# SparkFun_Dev_ESP32_C3.net
KiCad netlist of a schematic drawn in EAGLE
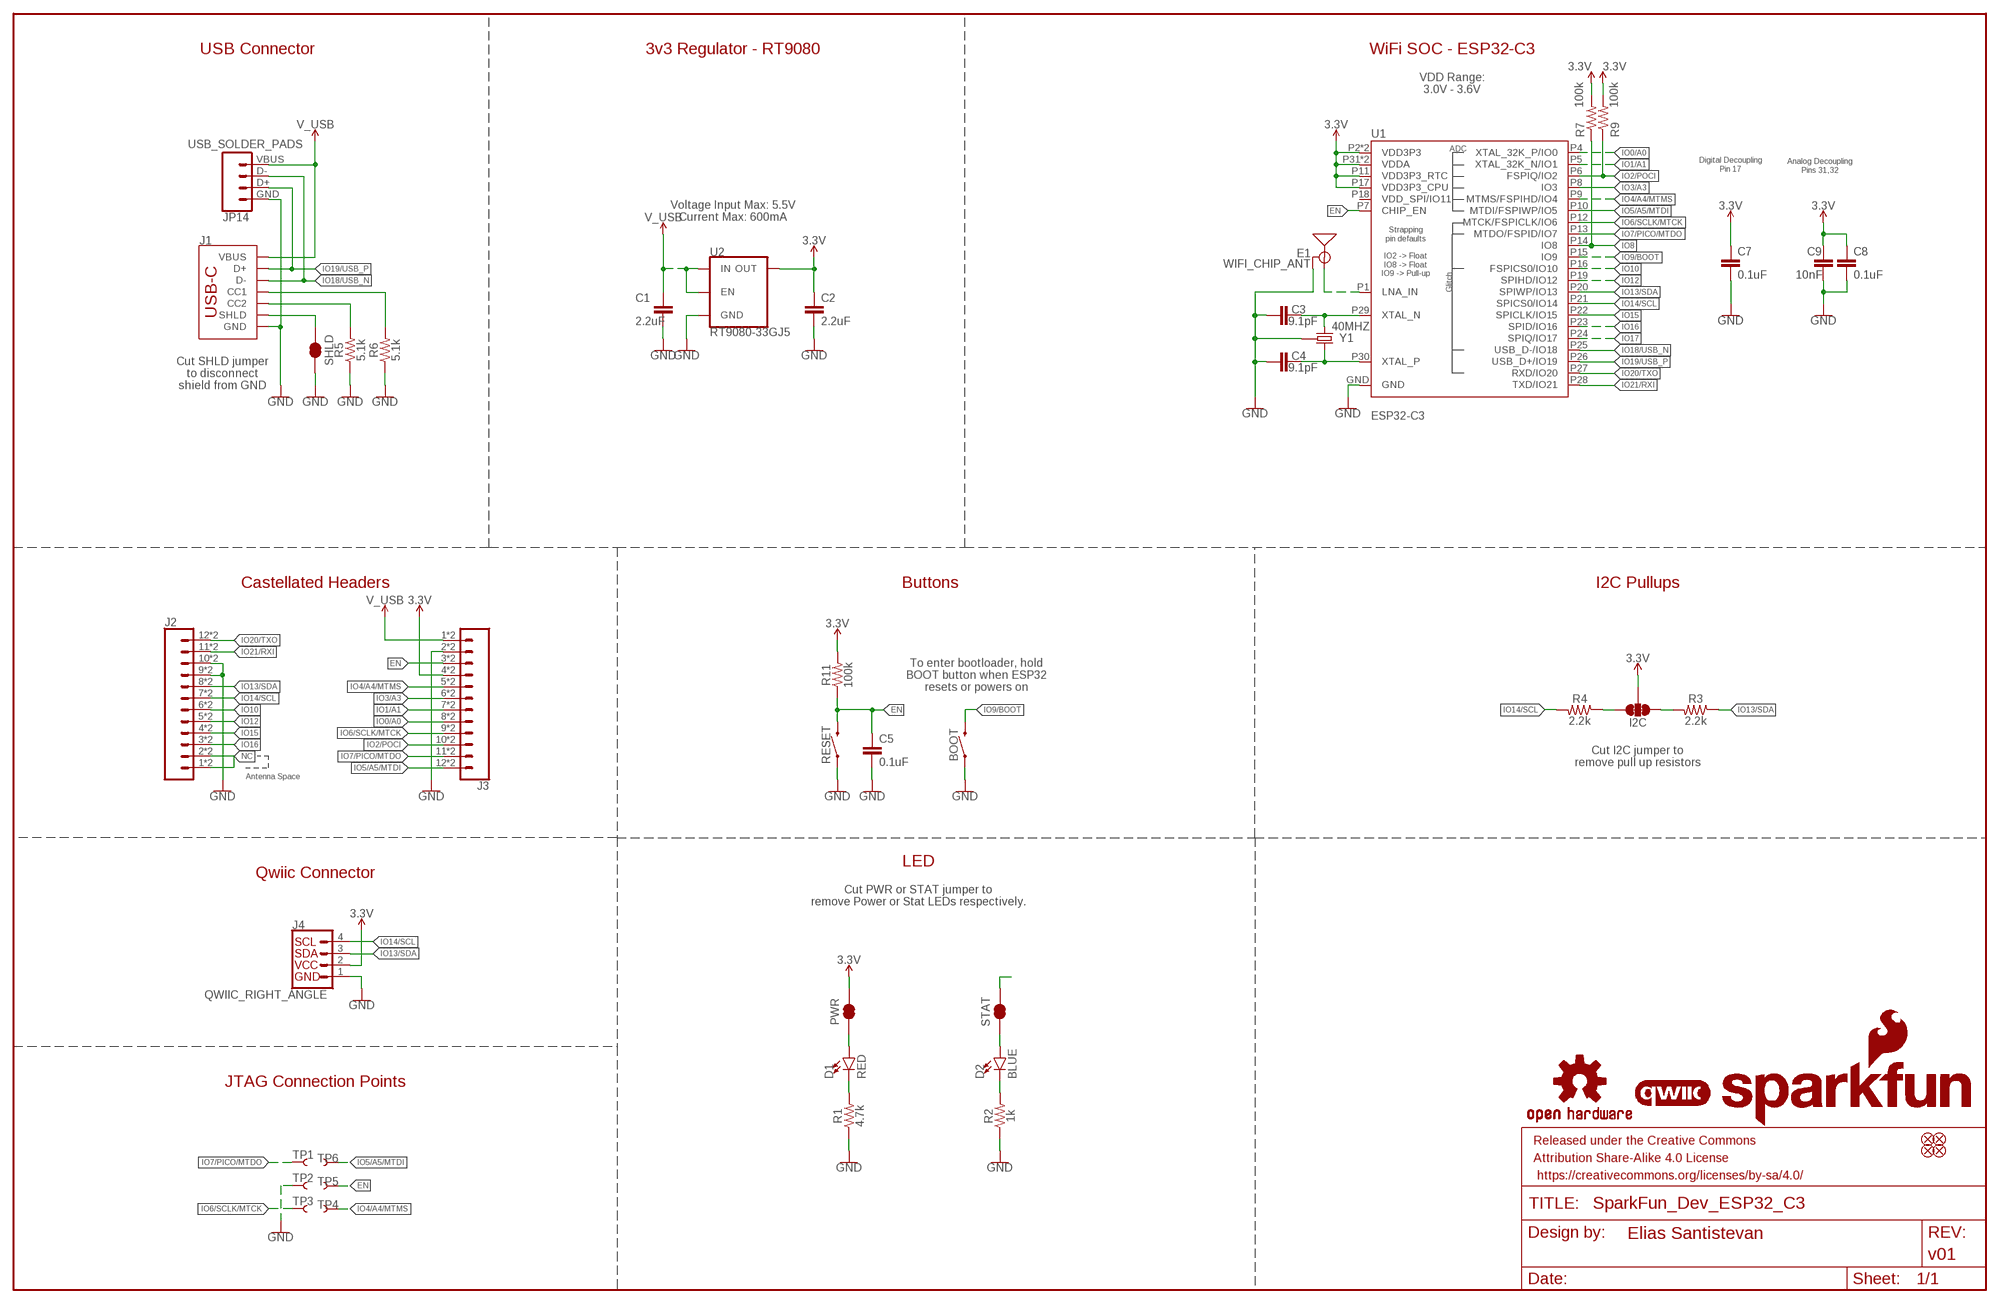
[diagram p0: schematic, sheet 1]

(export (version "E")
  (design (tool "Eeschema 10.0.6"))
  (components
    (comp (ref "BOOT")
      (value "MOMENTARY-SWITCH-SPST-SMD-4.6X2.8MM")
      (footprint "eagle-import:TACTILE_SWITCH_SMD_4.6X2.8MM")
      (libsource (lib "eagle-import") (part "MOMENTARY-SWITCH-SPST-SMD-4.6X2.8MM"))
    )
    (comp (ref "C1")
      (value "2.2uF")
      (footprint "eagle-import:0402-TIGHT")
      (libsource (lib "eagle-import") (part "2.2UF-0402_TIGHT-10V-10%-X5R"))
    )
    (comp (ref "C2")
      (value "2.2uF")
      (footprint "eagle-import:0402-TIGHT")
      (libsource (lib "eagle-import") (part "2.2UF-0402_TIGHT-10V-10%-X5R"))
    )
    (comp (ref "C3")
      (value "9.1pF")
      (footprint "eagle-import:0402-TIGHT")
      (fields (field (name "MOUSER_PART") "609-500R07S9R1CV4T"))
      (libsource (lib "eagle-import") (part "9.1PF-0402-TIGHT"))
    )
    (comp (ref "C4")
      (value "9.1pF")
      (footprint "eagle-import:0402-TIGHT")
      (fields (field (name "MOUSER_PART") "609-500R07S9R1CV4T"))
      (libsource (lib "eagle-import") (part "9.1PF-0402-TIGHT"))
    )
    (comp (ref "C5")
      (value "0.1uF")
      (footprint "eagle-import:0402-TIGHT")
      (libsource (lib "eagle-import") (part "0.1UF-0402T-6.3V-10%-X7R"))
    )
    (comp (ref "C7")
      (value "0.1uF")
      (footprint "eagle-import:0402-TIGHT")
      (libsource (lib "eagle-import") (part "0.1UF-0402T-16V-10%"))
    )
    (comp (ref "C8")
      (value "0.1uF")
      (footprint "eagle-import:0402-TIGHT")
      (libsource (lib "eagle-import") (part "0.1UF-0402T-16V-10%"))
    )
    (comp (ref "C9")
      (value "10nF")
      (footprint "eagle-import:0402-TIGHT")
      (libsource (lib "eagle-import") (part "10NF-0402T-25V-10%"))
    )
    (comp (ref "D1")
      (value "RED")
      (footprint "eagle-import:LED-0603")
      (libsource (lib "eagle-import") (part "LED-RED_0603-KB"))
    )
    (comp (ref "D2")
      (value "BLUE")
      (footprint "eagle-import:LED-0603")
      (libsource (lib "eagle-import") (part "LED-BLUE0603"))
    )
    (comp (ref "E1")
      (value "WIFI_CHIP_ANT")
      (footprint "eagle-import:CHIP_ANT_NO_COURTYARD")
      (libsource (lib "eagle-import") (part "WIFI_CHIP_ANT"))
    )
    (comp (ref "FD1")
      (value "FIDUCIALUFIDUCIAL")
      (footprint "eagle-import:FIDUCIAL-MICRO")
      (libsource (lib "eagle-import") (part "FIDUCIALUFIDUCIAL"))
    )
    (comp (ref "FD2")
      (value "FIDUCIALUFIDUCIAL")
      (footprint "eagle-import:FIDUCIAL-MICRO")
      (libsource (lib "eagle-import") (part "FIDUCIALUFIDUCIAL"))
    )
    (comp (ref "FD3")
      (value "FIDUCIALUFIDUCIAL")
      (footprint "eagle-import:FIDUCIAL-MICRO")
      (libsource (lib "eagle-import") (part "FIDUCIALUFIDUCIAL"))
    )
    (comp (ref "FD4")
      (value "FIDUCIALUFIDUCIAL")
      (footprint "eagle-import:FIDUCIAL-MICRO")
      (libsource (lib "eagle-import") (part "FIDUCIALUFIDUCIAL"))
    )
    (comp (ref "FRAME2")
      (value "FRAME-LEDGER")
      (footprint "eagle-import:CREATIVE_COMMONS")
      (fields (field (name "DESIGNER") "Elias Santistevan") (field (name "REV") "v01"))
      (libsource (lib "eagle-import") (part "FRAME-LEDGER"))
    )
    (comp (ref "I2C")
      (value "JUMPER-SMT_3_2-NC_TRACE_SILK")
      (footprint "eagle-import:SMT-JUMPER_3_2-NC_TRACE_SILK")
      (libsource (lib "eagle-import") (part "JUMPER-SMT_3_2-NC_TRACE_SILK"))
    )
    (comp (ref "J1")
      (value "USB Female Type C Connector")
      (footprint "eagle-import:USB-C-16P_4LAYER-PADS")
      (libsource (lib "eagle-import") (part "USB_C_4-LAYER_PADS"))
    )
    (comp (ref "J2")
      (value "CONN_12CASTELLATED")
      (footprint "eagle-import:1X12_CASTELLATED")
      (libsource (lib "eagle-import") (part "CONN_12CASTELLATED"))
    )
    (comp (ref "J3")
      (value "CONN_12CASTELLATED")
      (footprint "eagle-import:1X12_CASTELLATED")
      (libsource (lib "eagle-import") (part "CONN_12CASTELLATED"))
    )
    (comp (ref "J4")
      (value "QWIIC_RIGHT_ANGLE")
      (footprint "eagle-import:JST04_1MM_RA")
      (libsource (lib "eagle-import") (part "QWIIC_CONNECTORJS-1MM"))
    )
    (comp (ref "JP14")
      (value "USB_SOLDER_PADS")
      (footprint "eagle-import:USB-SOLDER-PADS")
      (libsource (lib "eagle-import") (part "USB_SOLDER_PADS"))
    )
    (comp (ref "LOGO1")
      (value "SFE_LOGO_NAME_FLAMEBLANK")
      (footprint "eagle-import:BLANK")
      (libsource (lib "eagle-import") (part "SFE_LOGO_NAME_FLAMEBLANK"))
    )
    (comp (ref "LOGO2")
      (value "QWIIC_LOGO_3MM")
      (footprint "eagle-import:QWIIC_3MM")
      (libsource (lib "eagle-import") (part "QWIIC_LOGO_3MM"))
    )
    (comp (ref "LOGO3")
      (value "OSHW-LOGOS")
      (footprint "eagle-import:OSHW-LOGO-S")
      (libsource (lib "eagle-import") (part "OSHW-LOGOS"))
    )
    (comp (ref "PWR")
      (value "JUMPER-SMT_2_NC_TRACE_SILK")
      (footprint "eagle-import:SMT-JUMPER_2_NC_TRACE_SILK")
      (libsource (lib "eagle-import") (part "JUMPER-SMT_2_NC_TRACE_SILK"))
    )
    (comp (ref "R1")
      (value "4.7k")
      (footprint "eagle-import:0402-TIGHT")
      (libsource (lib "eagle-import") (part "4.7KOHM-0402T-1/16W-1%"))
    )
    (comp (ref "R2")
      (value "1k")
      (footprint "eagle-import:0402-TIGHT")
      (libsource (lib "eagle-import") (part "1KOHM-0402T-1/16W-1%"))
    )
    (comp (ref "R3")
      (value "2.2k")
      (footprint "eagle-import:0402-TIGHT")
      (libsource (lib "eagle-import") (part "2.2KOHM-0402T-1/16W-1%"))
    )
    (comp (ref "R4")
      (value "2.2k")
      (footprint "eagle-import:0402-TIGHT")
      (libsource (lib "eagle-import") (part "2.2KOHM-0402T-1/16W-1%"))
    )
    (comp (ref "R5")
      (value "5.1k")
      (footprint "eagle-import:0402-TIGHT")
      (libsource (lib "eagle-import") (part "5.1KOHM-0402T-1/16W-1%"))
    )
    (comp (ref "R6")
      (value "5.1k")
      (footprint "eagle-import:0402-TIGHT")
      (libsource (lib "eagle-import") (part "5.1KOHM-0402T-1/16W-1%"))
    )
    (comp (ref "R7")
      (value "100k")
      (footprint "eagle-import:0402-TIGHT")
      (libsource (lib "eagle-import") (part "100KOHM-0402T-1/16W-1%"))
    )
    (comp (ref "R9")
      (value "100k")
      (footprint "eagle-import:0402-TIGHT")
      (libsource (lib "eagle-import") (part "100KOHM-0402T-1/16W-1%"))
    )
    (comp (ref "R11")
      (value "100k")
      (footprint "eagle-import:0402-TIGHT")
      (libsource (lib "eagle-import") (part "100KOHM-0402T-1/16W-1%"))
    )
    (comp (ref "RESET")
      (value "MOMENTARY-SWITCH-SPST-SMD-4.6X2.8MM")
      (footprint "eagle-import:TACTILE_SWITCH_SMD_4.6X2.8MM")
      (libsource (lib "eagle-import") (part "MOMENTARY-SWITCH-SPST-SMD-4.6X2.8MM"))
    )
    (comp (ref "SHLD")
      (value "JUMPER-SMT_2_NC_TRACE_SILK")
      (footprint "eagle-import:SMT-JUMPER_2_NC_TRACE_SILK")
      (libsource (lib "eagle-import") (part "JUMPER-SMT_2_NC_TRACE_SILK"))
    )
    (comp (ref "STAT")
      (value "JUMPER-SMT_2_NC_TRACE_SILK")
      (footprint "eagle-import:SMT-JUMPER_2_NC_TRACE_SILK")
      (libsource (lib "eagle-import") (part "JUMPER-SMT_2_NC_TRACE_SILK"))
    )
    (comp (ref "TP1")
      (value "TEST-POINT3X5")
      (footprint "eagle-import:PAD.03X.05")
      (libsource (lib "eagle-import") (part "TEST-POINT3X5"))
    )
    (comp (ref "TP2")
      (value "TEST-POINT3X5")
      (footprint "eagle-import:PAD.03X.05")
      (libsource (lib "eagle-import") (part "TEST-POINT3X5"))
    )
    (comp (ref "TP3")
      (value "TEST-POINT3X5")
      (footprint "eagle-import:PAD.03X.05")
      (libsource (lib "eagle-import") (part "TEST-POINT3X5"))
    )
    (comp (ref "TP4")
      (value "TEST-POINT3X5")
      (footprint "eagle-import:PAD.03X.05")
      (libsource (lib "eagle-import") (part "TEST-POINT3X5"))
    )
    (comp (ref "TP5")
      (value "TEST-POINT3X5")
      (footprint "eagle-import:PAD.03X.05")
      (libsource (lib "eagle-import") (part "TEST-POINT3X5"))
    )
    (comp (ref "TP6")
      (value "TEST-POINT3X5")
      (footprint "eagle-import:PAD.03X.05")
      (libsource (lib "eagle-import") (part "TEST-POINT3X5"))
    )
    (comp (ref "U1")
      (value "ESP32-C3")
      (footprint "eagle-import:QFN32")
      (libsource (lib "eagle-import") (part "ESP32-C3"))
    )
    (comp (ref "U2")
      (value "RT9080-33GJ5")
      (footprint "eagle-import:SOT23-5")
      (libsource (lib "eagle-import") (part "V_REG_RT9080"))
    )
    (comp (ref "Y1")
      (value "40MHZ")
      (footprint "eagle-import:CRYSTAL-SMD-2X2.5MM")
      (libsource (lib "eagle-import") (part "CRYSTAL-40MHZ-SMD-2X2.5MM"))
    )
  )
  (nets
    (net (code "1") (name "3.3V") (class "Default")
      (node (ref "C2") (pin "1") (pinfunction "1_1") (pintype "passive"))
      (node (ref "C7") (pin "1") (pinfunction "1_1") (pintype "passive"))
      (node (ref "C8") (pin "1") (pinfunction "1_1") (pintype "passive"))
      (node (ref "C9") (pin "1") (pinfunction "1_1") (pintype "passive"))
      (node (ref "I2C") (pin "2") (pinfunction "2_2") (pintype "passive"))
      (node (ref "J3") (pin "4") (pinfunction "4_4") (pintype "passive"))
      (node (ref "J3") (pin "4B") (pinfunction "4_4B") (pintype "passive"))
      (node (ref "J4") (pin "2") (pinfunction "2_2") (pintype "power_in"))
      (node (ref "PWR") (pin "2") (pinfunction "2_2") (pintype "passive"))
      (node (ref "R11") (pin "2") (pinfunction "2_2") (pintype "passive"))
      (node (ref "R7") (pin "2") (pinfunction "2_2") (pintype "passive"))
      (node (ref "R9") (pin "2") (pinfunction "2_2") (pintype "passive"))
      (node (ref "U1") (pin "P11") (pinfunction "VDD3P3_RTC_P11") (pintype "bidirectional"))
      (node (ref "U1") (pin "P17") (pinfunction "VDD3P3_CPU_P17") (pintype "bidirectional"))
      (node (ref "U1") (pin "P2") (pinfunction "VDD3P3_P2") (pintype "bidirectional"))
      (node (ref "U1") (pin "P3") (pinfunction "VDD3P3_P3") (pintype "bidirectional"))
      (node (ref "U1") (pin "P31") (pinfunction "VDDA_P31") (pintype "bidirectional"))
      (node (ref "U1") (pin "P32") (pinfunction "VDDA_P32") (pintype "bidirectional"))
      (node (ref "U2") (pin "5") (pinfunction "OUT_5") (pintype "passive"))
    )
    (net (code "2") (name "EN") (class "Default")
      (node (ref "C5") (pin "1") (pinfunction "1_1") (pintype "passive"))
      (node (ref "J3") (pin "3") (pinfunction "3_3") (pintype "passive"))
      (node (ref "J3") (pin "3B") (pinfunction "3_3B") (pintype "passive"))
      (node (ref "R11") (pin "1") (pinfunction "1_1") (pintype "passive"))
      (node (ref "RESET") (pin "3") (pinfunction "2_3") (pintype "passive"))
      (node (ref "RESET") (pin "4") (pinfunction "2_4") (pintype "passive"))
      (node (ref "TP5") (pin "1") (pinfunction "1_1") (pintype "bidirectional"))
      (node (ref "U1") (pin "P7") (pinfunction "CHIP_EN_P7") (pintype "bidirectional"))
    )
    (net (code "3") (name "GND") (class "Default")
      (node (ref "BOOT") (pin "1") (pinfunction "1_1") (pintype "passive"))
      (node (ref "BOOT") (pin "2") (pinfunction "1_2") (pintype "passive"))
      (node (ref "C1") (pin "2") (pinfunction "2_2") (pintype "passive"))
      (node (ref "C2") (pin "2") (pinfunction "2_2") (pintype "passive"))
      (node (ref "C3") (pin "1") (pinfunction "1_1") (pintype "passive"))
      (node (ref "C4") (pin "1") (pinfunction "1_1") (pintype "passive"))
      (node (ref "C5") (pin "2") (pinfunction "2_2") (pintype "passive"))
      (node (ref "C7") (pin "2") (pinfunction "2_2") (pintype "passive"))
      (node (ref "C8") (pin "2") (pinfunction "2_2") (pintype "passive"))
      (node (ref "C9") (pin "2") (pinfunction "2_2") (pintype "passive"))
      (node (ref "E1") (pin "P3") (pinfunction "GND_P3") (pintype "bidirectional"))
      (node (ref "E1") (pin "P4") (pinfunction "GND_P4") (pintype "bidirectional"))
      (node (ref "J1") (pin "GND") (pinfunction "GND_GND") (pintype "bidirectional"))
      (node (ref "J1") (pin "GND2") (pinfunction "GND_GND2") (pintype "bidirectional"))
      (node (ref "J2") (pin "10") (pinfunction "10_10") (pintype "passive"))
      (node (ref "J2") (pin "10B") (pinfunction "10_10B") (pintype "passive"))
      (node (ref "J2") (pin "9") (pinfunction "9_9") (pintype "passive"))
      (node (ref "J2") (pin "9B") (pinfunction "9_9B") (pintype "passive"))
      (node (ref "J3") (pin "2") (pinfunction "2_2") (pintype "passive"))
      (node (ref "J3") (pin "2B") (pinfunction "2_2B") (pintype "passive"))
      (node (ref "J4") (pin "1") (pinfunction "1_1") (pintype "power_in"))
      (node (ref "JP14") (pin "GND") (pinfunction "4_GND") (pintype "passive"))
      (node (ref "R1") (pin "1") (pinfunction "1_1") (pintype "passive"))
      (node (ref "R2") (pin "1") (pinfunction "1_1") (pintype "passive"))
      (node (ref "R5") (pin "1") (pinfunction "1_1") (pintype "passive"))
      (node (ref "R6") (pin "1") (pinfunction "1_1") (pintype "passive"))
      (node (ref "RESET") (pin "1") (pinfunction "1_1") (pintype "passive"))
      (node (ref "RESET") (pin "2") (pinfunction "1_2") (pintype "passive"))
      (node (ref "SHLD") (pin "2") (pinfunction "2_2") (pintype "passive"))
      (node (ref "TP2") (pin "1") (pinfunction "1_1") (pintype "bidirectional"))
      (node (ref "U1") (pin "GND") (pinfunction "GND_GND") (pintype "bidirectional"))
      (node (ref "U2") (pin "2") (pinfunction "GND_2") (pintype "input"))
      (node (ref "Y1") (pin "P2") (pinfunction "GND_P2") (pintype "power_in"))
      (node (ref "Y1") (pin "P4") (pinfunction "GND_P4") (pintype "power_in"))
    )
    (net (code "4") (name "IO0{slash}A0") (class "Default")
      (node (ref "J3") (pin "8") (pinfunction "8_8") (pintype "passive"))
      (node (ref "J3") (pin "8B") (pinfunction "8_8B") (pintype "passive"))
      (node (ref "U1") (pin "P4") (pinfunction "XTAL_32K_P/IO0_P4") (pintype "bidirectional"))
    )
    (net (code "5") (name "IO1{slash}A1") (class "Default")
      (node (ref "J3") (pin "7") (pinfunction "7_7") (pintype "passive"))
      (node (ref "J3") (pin "7B") (pinfunction "7_7B") (pintype "passive"))
      (node (ref "U1") (pin "P5") (pinfunction "XTAL_32K_N/IO1_P5") (pintype "bidirectional"))
    )
    (net (code "6") (name "IO2{slash}POCI") (class "Default")
      (node (ref "J3") (pin "10") (pinfunction "10_10") (pintype "passive"))
      (node (ref "J3") (pin "10B") (pinfunction "10_10B") (pintype "passive"))
      (node (ref "R9") (pin "1") (pinfunction "1_1") (pintype "passive"))
      (node (ref "U1") (pin "P6") (pinfunction "FSPIQ/IO2_P6") (pintype "bidirectional"))
    )
    (net (code "7") (name "IO3{slash}A3") (class "Default")
      (node (ref "J3") (pin "6") (pinfunction "6_6") (pintype "passive"))
      (node (ref "J3") (pin "6B") (pinfunction "6_6B") (pintype "passive"))
      (node (ref "U1") (pin "P8") (pinfunction "IO3_P8") (pintype "bidirectional"))
    )
    (net (code "8") (name "IO4{slash}A4{slash}MTMS") (class "Default")
      (node (ref "J3") (pin "5") (pinfunction "5_5") (pintype "passive"))
      (node (ref "J3") (pin "5B") (pinfunction "5_5B") (pintype "passive"))
      (node (ref "TP4") (pin "1") (pinfunction "1_1") (pintype "bidirectional"))
      (node (ref "U1") (pin "P9") (pinfunction "MTMS/FSPIHD/IO4_P9") (pintype "bidirectional"))
    )
    (net (code "9") (name "IO5{slash}A5{slash}MTDI") (class "Default")
      (node (ref "J3") (pin "12") (pinfunction "12_12") (pintype "passive"))
      (node (ref "J3") (pin "12B") (pinfunction "12_12B") (pintype "passive"))
      (node (ref "TP6") (pin "1") (pinfunction "1_1") (pintype "bidirectional"))
      (node (ref "U1") (pin "P10") (pinfunction "MTDI/FSPIWP/IO5_P10") (pintype "bidirectional"))
    )
    (net (code "10") (name "IO6{slash}SCLK{slash}MTCK") (class "Default")
      (node (ref "J3") (pin "9") (pinfunction "9_9") (pintype "passive"))
      (node (ref "J3") (pin "9B") (pinfunction "9_9B") (pintype "passive"))
      (node (ref "TP3") (pin "1") (pinfunction "1_1") (pintype "bidirectional"))
      (node (ref "U1") (pin "P12") (pinfunction "MTCK/FSPICLK/IO6_P12") (pintype "bidirectional"))
    )
    (net (code "11") (name "IO7{slash}PICO{slash}MTDO") (class "Default")
      (node (ref "J3") (pin "11") (pinfunction "11_11") (pintype "passive"))
      (node (ref "J3") (pin "11B") (pinfunction "11_11B") (pintype "passive"))
      (node (ref "TP1") (pin "1") (pinfunction "1_1") (pintype "bidirectional"))
      (node (ref "U1") (pin "P13") (pinfunction "MTDO/FSPID/IO7_P13") (pintype "bidirectional"))
    )
    (net (code "12") (name "IO8") (class "Default")
      (node (ref "R7") (pin "1") (pinfunction "1_1") (pintype "passive"))
      (node (ref "U1") (pin "P14") (pinfunction "IO8_P14") (pintype "bidirectional"))
    )
    (net (code "13") (name "IO9{slash}BOOT") (class "Default")
      (node (ref "BOOT") (pin "3") (pinfunction "2_3") (pintype "passive"))
      (node (ref "BOOT") (pin "4") (pinfunction "2_4") (pintype "passive"))
      (node (ref "U1") (pin "P15") (pinfunction "IO9_P15") (pintype "bidirectional"))
    )
    (net (code "14") (name "IO10") (class "Default")
      (node (ref "J2") (pin "6") (pinfunction "6_6") (pintype "passive"))
      (node (ref "J2") (pin "6B") (pinfunction "6_6B") (pintype "passive"))
      (node (ref "U1") (pin "P16") (pinfunction "FSPICS0/IO10_P16") (pintype "bidirectional"))
    )
    (net (code "15") (name "IO12") (class "Default")
      (node (ref "J2") (pin "5") (pinfunction "5_5") (pintype "passive"))
      (node (ref "J2") (pin "5B") (pinfunction "5_5B") (pintype "passive"))
      (node (ref "U1") (pin "P19") (pinfunction "SPIHD/IO12_P19") (pintype "bidirectional"))
    )
    (net (code "16") (name "IO13{slash}SDA") (class "Default")
      (node (ref "J2") (pin "8") (pinfunction "8_8") (pintype "passive"))
      (node (ref "J2") (pin "8B") (pinfunction "8_8B") (pintype "passive"))
      (node (ref "J4") (pin "3") (pinfunction "3_3") (pintype "passive"))
      (node (ref "R3") (pin "1") (pinfunction "1_1") (pintype "passive"))
      (node (ref "U1") (pin "P20") (pinfunction "SPIWP/IO13_P20") (pintype "bidirectional"))
    )
    (net (code "17") (name "IO14{slash}SCL") (class "Default")
      (node (ref "J2") (pin "7") (pinfunction "7_7") (pintype "passive"))
      (node (ref "J2") (pin "7B") (pinfunction "7_7B") (pintype "passive"))
      (node (ref "J4") (pin "4") (pinfunction "4_4") (pintype "passive"))
      (node (ref "R4") (pin "2") (pinfunction "2_2") (pintype "passive"))
      (node (ref "U1") (pin "P21") (pinfunction "SPICS0/IO14_P21") (pintype "bidirectional"))
    )
    (net (code "18") (name "IO15") (class "Default")
      (node (ref "J2") (pin "4") (pinfunction "4_4") (pintype "passive"))
      (node (ref "J2") (pin "4B") (pinfunction "4_4B") (pintype "passive"))
      (node (ref "U1") (pin "P22") (pinfunction "SPICLK/IO15_P22") (pintype "bidirectional"))
    )
    (net (code "19") (name "IO16") (class "Default")
      (node (ref "J2") (pin "3") (pinfunction "3_3") (pintype "passive"))
      (node (ref "J2") (pin "3B") (pinfunction "3_3B") (pintype "passive"))
      (node (ref "U1") (pin "P23") (pinfunction "SPID/IO16_P23") (pintype "bidirectional"))
    )
    (net (code "20") (name "IO17") (class "Default")
      (node (ref "U1") (pin "P24") (pinfunction "SPIQ/IO17_P24") (pintype "bidirectional"))
    )
    (net (code "21") (name "IO18{slash}USB_N") (class "Default")
      (node (ref "J1") (pin "A7") (pinfunction "D-_A7") (pintype "bidirectional"))
      (node (ref "J1") (pin "B7") (pinfunction "D-_B7") (pintype "bidirectional"))
      (node (ref "JP14") (pin "D-") (pinfunction "2_D-") (pintype "passive"))
      (node (ref "U1") (pin "P25") (pinfunction "USB_D-/IO18_P25") (pintype "bidirectional"))
    )
    (net (code "22") (name "IO19{slash}USB_P") (class "Default")
      (node (ref "J1") (pin "A6") (pinfunction "D+_A6") (pintype "bidirectional"))
      (node (ref "J1") (pin "B6") (pinfunction "D+_B6") (pintype "bidirectional"))
      (node (ref "JP14") (pin "D+") (pinfunction "3_D+") (pintype "passive"))
      (node (ref "U1") (pin "P26") (pinfunction "USB_D+/IO19_P26") (pintype "bidirectional"))
    )
    (net (code "23") (name "IO20{slash}TXO") (class "Default")
      (node (ref "J2") (pin "12") (pinfunction "12_12") (pintype "passive"))
      (node (ref "J2") (pin "12B") (pinfunction "12_12B") (pintype "passive"))
      (node (ref "U1") (pin "P27") (pinfunction "RXD/IO20_P27") (pintype "bidirectional"))
    )
    (net (code "24") (name "IO21{slash}RXI") (class "Default")
      (node (ref "J2") (pin "11") (pinfunction "11_11") (pintype "passive"))
      (node (ref "J2") (pin "11B") (pinfunction "11_11B") (pintype "passive"))
      (node (ref "U1") (pin "P28") (pinfunction "TXD/IO21_P28") (pintype "bidirectional"))
    )
    (net (code "25") (name "NC") (class "Default")
      (node (ref "J2") (pin "1") (pinfunction "1_1") (pintype "passive"))
      (node (ref "J2") (pin "1B") (pinfunction "1_1B") (pintype "passive"))
      (node (ref "J2") (pin "2") (pinfunction "2_2") (pintype "passive"))
      (node (ref "J2") (pin "2B") (pinfunction "2_2B") (pintype "passive"))
    )
    (net (code "26") (name "Net-(D1-PadA)") (class "Default")
      (node (ref "D1") (pin "A") (pinfunction "A_A") (pintype "passive"))
      (node (ref "PWR") (pin "1") (pinfunction "1_1") (pintype "passive"))
    )
    (net (code "27") (name "Net-(D1-PadC)") (class "Default")
      (node (ref "D1") (pin "C") (pinfunction "C_C") (pintype "passive"))
      (node (ref "R1") (pin "2") (pinfunction "2_2") (pintype "passive"))
    )
    (net (code "28") (name "Net-(D2-PadA)") (class "Default")
      (node (ref "D2") (pin "A") (pinfunction "A_A") (pintype "passive"))
      (node (ref "STAT") (pin "1") (pinfunction "1_1") (pintype "passive"))
    )
    (net (code "29") (name "Net-(D2-PadC)") (class "Default")
      (node (ref "D2") (pin "C") (pinfunction "C_C") (pintype "passive"))
      (node (ref "R2") (pin "2") (pinfunction "2_2") (pintype "passive"))
    )
    (net (code "30") (name "Net-(E1-SIGNAL)") (class "Default")
      (node (ref "E1") (pin "P1") (pinfunction "SIGNAL_P1") (pintype "bidirectional"))
      (node (ref "U1") (pin "P1") (pinfunction "LNA_IN_P1") (pintype "bidirectional"))
    )
    (net (code "31") (name "Net-(I2C-Pad1)") (class "Default")
      (node (ref "I2C") (pin "1") (pinfunction "1_1") (pintype "passive"))
      (node (ref "R4") (pin "1") (pinfunction "1_1") (pintype "passive"))
    )
    (net (code "32") (name "Net-(I2C-Pad3)") (class "Default")
      (node (ref "I2C") (pin "3") (pinfunction "3_3") (pintype "passive"))
      (node (ref "R3") (pin "2") (pinfunction "2_2") (pintype "passive"))
    )
    (net (code "33") (name "Net-(J1-CC1)") (class "Default")
      (node (ref "J1") (pin "A5") (pinfunction "CC1_A5") (pintype "bidirectional"))
      (node (ref "R6") (pin "2") (pinfunction "2_2") (pintype "passive"))
    )
    (net (code "34") (name "Net-(J1-CC2)") (class "Default")
      (node (ref "J1") (pin "B5") (pinfunction "CC2_B5") (pintype "bidirectional"))
      (node (ref "R5") (pin "2") (pinfunction "2_2") (pintype "passive"))
    )
    (net (code "35") (name "Net-(J1-SHLD-PadSHLD1)") (class "Default")
      (node (ref "J1") (pin "SHLD1") (pinfunction "SHLD_SHLD1") (pintype "bidirectional"))
      (node (ref "J1") (pin "SHLD2") (pinfunction "SHLD_SHLD2") (pintype "bidirectional"))
      (node (ref "J1") (pin "SHLD3") (pinfunction "SHLD_SHLD3") (pintype "bidirectional"))
      (node (ref "J1") (pin "SHLD4") (pinfunction "SHLD_SHLD4") (pintype "bidirectional"))
      (node (ref "SHLD") (pin "1") (pinfunction "1_1") (pintype "passive"))
    )
    (net (code "36") (name "Net-(U1-XTAL_N)") (class "Default")
      (node (ref "C3") (pin "2") (pinfunction "2_2") (pintype "passive"))
      (node (ref "U1") (pin "P29") (pinfunction "XTAL_N_P29") (pintype "bidirectional"))
      (node (ref "Y1") (pin "P1") (pinfunction "1_P1") (pintype "passive"))
    )
    (net (code "37") (name "Net-(U1-XTAL_P)") (class "Default")
      (node (ref "C4") (pin "2") (pinfunction "2_2") (pintype "passive"))
      (node (ref "U1") (pin "P30") (pinfunction "XTAL_P_P30") (pintype "bidirectional"))
      (node (ref "Y1") (pin "P3") (pinfunction "2_P3") (pintype "passive"))
    )
    (net (code "38") (name "V_USB") (class "Default")
      (node (ref "C1") (pin "1") (pinfunction "1_1") (pintype "passive"))
      (node (ref "J1") (pin "VBUS1") (pinfunction "VBUS_VBUS1") (pintype "bidirectional"))
      (node (ref "J1") (pin "VBUS2") (pinfunction "VBUS_VBUS2") (pintype "bidirectional"))
      (node (ref "J3") (pin "1") (pinfunction "1_1") (pintype "passive"))
      (node (ref "J3") (pin "1B") (pinfunction "1_1B") (pintype "passive"))
      (node (ref "JP14") (pin "VBUS") (pinfunction "1_VBUS") (pintype "passive"))
      (node (ref "U2") (pin "1") (pinfunction "IN_1") (pintype "input"))
      (node (ref "U2") (pin "3") (pinfunction "EN_3") (pintype "input"))
    )
    (net (code "39") (name "unconnected-(STAT-Pad2)") (class "Default")
      (node (ref "STAT") (pin "2") (pinfunction "2_2") (pintype "passive"))
    )
    (net (code "40") (name "unconnected-(U1-VDD_SPI{slash}IO11-PadP18)") (class "Default")
      (node (ref "U1") (pin "P18") (pinfunction "VDD_SPI/IO11_P18") (pintype "bidirectional"))
    )
  )
)
